# design.net
KiCad netlist of a schematic drawn in Altium Designer
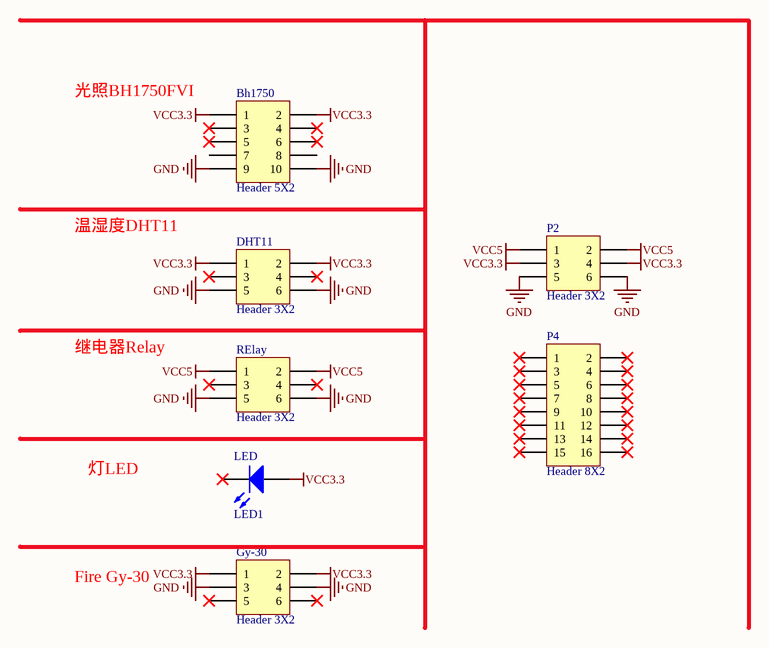
[diagram p0: 智能实验室传感器底板.SchDoc]

(export (version "E")
  (design (tool "Eeschema 10.0.6"))
  (components
    (comp (ref "Bh1750")
      (value "Header 5X2")
      (footprint "HDR2X5")
      (description "Header, 5-Pin, Dual row")
      (fields (field (name "PUBLISHER") "Altium Limited"))
      (libsource (lib "Miscellaneous Connectors") (part "Header 5X2"))
    )
    (comp (ref "DHT11")
      (value "Header 3X2")
      (footprint "HDR2X3")
      (description "Header, 3-Pin, Dual row")
      (fields (field (name "PUBLISHER") "Altium Limited"))
      (libsource (lib "Miscellaneous Connectors") (part "Header 3X2"))
    )
    (comp (ref "Gy-30")
      (value "Header 3X2")
      (footprint "HDR2X3")
      (description "Header, 3-Pin, Dual row")
      (fields (field (name "PUBLISHER") "Altium Limited"))
      (libsource (lib "Miscellaneous Connectors") (part "Header 3X2"))
    )
    (comp (ref "LED")
      (value "LED1")
      (footprint "LED-1")
      (description "Typical RED GaAs LED")
      (fields (field (name "PUBLISHER") "Altium Limited"))
      (libsource (lib "Miscellaneous Devices") (part "LED1"))
    )
    (comp (ref "P2")
      (value "Header 3X2")
      (footprint "HDR2X3")
      (description "Header, 3-Pin, Dual row")
      (fields (field (name "PUBLISHER") "Altium Limited"))
      (libsource (lib "Miscellaneous Connectors") (part "Header 3X2"))
    )
    (comp (ref "P4")
      (value "Header 8X2")
      (footprint "HDR2X8")
      (description "Header, 8-Pin, Dual row")
      (fields (field (name "PUBLISHER") "Altium Limited"))
      (libsource (lib "Miscellaneous Connectors") (part "Header 8X2"))
    )
    (comp (ref "RElay")
      (value "Header 3X2")
      (footprint "HDR2X3")
      (description "Header, 3-Pin, Dual row")
      (fields (field (name "PUBLISHER") "Altium Limited"))
      (libsource (lib "Miscellaneous Connectors") (part "Header 3X2"))
    )
  )
  (nets
    (net (code "1") (name "GND") (class "Default")
      (node (ref "Bh1750") (pin "10") (pinfunction "10_10") (pintype "passive"))
      (node (ref "Bh1750") (pin "9") (pinfunction "9_9") (pintype "passive"))
      (node (ref "DHT11") (pin "5") (pinfunction "5_5") (pintype "passive"))
      (node (ref "DHT11") (pin "6") (pinfunction "6_6") (pintype "passive"))
      (node (ref "Gy-30") (pin "3") (pinfunction "3_3") (pintype "passive"))
      (node (ref "Gy-30") (pin "4") (pinfunction "4_4") (pintype "passive"))
      (node (ref "P2") (pin "5") (pinfunction "5_5") (pintype "passive"))
      (node (ref "P2") (pin "6") (pinfunction "6_6") (pintype "passive"))
      (node (ref "RElay") (pin "5") (pinfunction "5_5") (pintype "passive"))
      (node (ref "RElay") (pin "6") (pinfunction "6_6") (pintype "passive"))
    )
    (net (code "2") (name "VCC3.3") (class "Default")
      (node (ref "Bh1750") (pin "1") (pinfunction "1_1") (pintype "passive"))
      (node (ref "Bh1750") (pin "2") (pinfunction "2_2") (pintype "passive"))
      (node (ref "DHT11") (pin "1") (pinfunction "1_1") (pintype "passive"))
      (node (ref "DHT11") (pin "2") (pinfunction "2_2") (pintype "passive"))
      (node (ref "Gy-30") (pin "1") (pinfunction "1_1") (pintype "passive"))
      (node (ref "Gy-30") (pin "2") (pinfunction "2_2") (pintype "passive"))
      (node (ref "LED") (pin "1") (pinfunction "A_1") (pintype "passive"))
      (node (ref "P2") (pin "3") (pinfunction "3_3") (pintype "passive"))
      (node (ref "P2") (pin "4") (pinfunction "4_4") (pintype "passive"))
    )
    (net (code "3") (name "VCC5") (class "Default")
      (node (ref "P2") (pin "1") (pinfunction "1_1") (pintype "passive"))
      (node (ref "P2") (pin "2") (pinfunction "2_2") (pintype "passive"))
      (node (ref "RElay") (pin "1") (pinfunction "1_1") (pintype "passive"))
      (node (ref "RElay") (pin "2") (pinfunction "2_2") (pintype "passive"))
    )
    (net (code "4") (name "unconnected-(Bh1750-Pad3)") (class "Default")
      (node (ref "Bh1750") (pin "3") (pinfunction "3_3") (pintype "passive+no_connect"))
    )
    (net (code "5") (name "unconnected-(Bh1750-Pad4)") (class "Default")
      (node (ref "Bh1750") (pin "4") (pinfunction "4_4") (pintype "passive+no_connect"))
    )
    (net (code "6") (name "unconnected-(Bh1750-Pad5)") (class "Default")
      (node (ref "Bh1750") (pin "5") (pinfunction "5_5") (pintype "passive+no_connect"))
    )
    (net (code "7") (name "unconnected-(Bh1750-Pad6)") (class "Default")
      (node (ref "Bh1750") (pin "6") (pinfunction "6_6") (pintype "passive+no_connect"))
    )
    (net (code "8") (name "unconnected-(Bh1750-Pad7)") (class "Default")
      (node (ref "Bh1750") (pin "7") (pinfunction "7_7") (pintype "passive"))
    )
    (net (code "9") (name "unconnected-(Bh1750-Pad8)") (class "Default")
      (node (ref "Bh1750") (pin "8") (pinfunction "8_8") (pintype "passive"))
    )
    (net (code "10") (name "unconnected-(DHT11-Pad3)") (class "Default")
      (node (ref "DHT11") (pin "3") (pinfunction "3_3") (pintype "passive+no_connect"))
    )
    (net (code "11") (name "unconnected-(DHT11-Pad4)") (class "Default")
      (node (ref "DHT11") (pin "4") (pinfunction "4_4") (pintype "passive+no_connect"))
    )
    (net (code "12") (name "unconnected-(Gy-30-Pad5)") (class "Default")
      (node (ref "Gy-30") (pin "5") (pinfunction "5_5") (pintype "passive+no_connect"))
    )
    (net (code "13") (name "unconnected-(Gy-30-Pad6)") (class "Default")
      (node (ref "Gy-30") (pin "6") (pinfunction "6_6") (pintype "passive+no_connect"))
    )
    (net (code "14") (name "unconnected-(LED-K-Pad2)") (class "Default")
      (node (ref "LED") (pin "2") (pinfunction "K_2") (pintype "passive+no_connect"))
    )
    (net (code "15") (name "unconnected-(P4-Pad1)") (class "Default")
      (node (ref "P4") (pin "1") (pinfunction "1_1") (pintype "passive+no_connect"))
    )
    (net (code "16") (name "unconnected-(P4-Pad2)") (class "Default")
      (node (ref "P4") (pin "2") (pinfunction "2_2") (pintype "passive+no_connect"))
    )
    (net (code "17") (name "unconnected-(P4-Pad3)") (class "Default")
      (node (ref "P4") (pin "3") (pinfunction "3_3") (pintype "passive+no_connect"))
    )
    (net (code "18") (name "unconnected-(P4-Pad4)") (class "Default")
      (node (ref "P4") (pin "4") (pinfunction "4_4") (pintype "passive+no_connect"))
    )
    (net (code "19") (name "unconnected-(P4-Pad5)") (class "Default")
      (node (ref "P4") (pin "5") (pinfunction "5_5") (pintype "passive+no_connect"))
    )
    (net (code "20") (name "unconnected-(P4-Pad6)") (class "Default")
      (node (ref "P4") (pin "6") (pinfunction "6_6") (pintype "passive+no_connect"))
    )
    (net (code "21") (name "unconnected-(P4-Pad7)") (class "Default")
      (node (ref "P4") (pin "7") (pinfunction "7_7") (pintype "passive+no_connect"))
    )
    (net (code "22") (name "unconnected-(P4-Pad8)") (class "Default")
      (node (ref "P4") (pin "8") (pinfunction "8_8") (pintype "passive+no_connect"))
    )
    (net (code "23") (name "unconnected-(P4-Pad9)") (class "Default")
      (node (ref "P4") (pin "9") (pinfunction "9_9") (pintype "passive+no_connect"))
    )
    (net (code "24") (name "unconnected-(P4-Pad10)") (class "Default")
      (node (ref "P4") (pin "10") (pinfunction "10_10") (pintype "passive+no_connect"))
    )
    (net (code "25") (name "unconnected-(P4-Pad11)") (class "Default")
      (node (ref "P4") (pin "11") (pinfunction "11_11") (pintype "passive+no_connect"))
    )
    (net (code "26") (name "unconnected-(P4-Pad12)") (class "Default")
      (node (ref "P4") (pin "12") (pinfunction "12_12") (pintype "passive+no_connect"))
    )
    (net (code "27") (name "unconnected-(P4-Pad13)") (class "Default")
      (node (ref "P4") (pin "13") (pinfunction "13_13") (pintype "passive+no_connect"))
    )
    (net (code "28") (name "unconnected-(P4-Pad14)") (class "Default")
      (node (ref "P4") (pin "14") (pinfunction "14_14") (pintype "passive+no_connect"))
    )
    (net (code "29") (name "unconnected-(P4-Pad15)") (class "Default")
      (node (ref "P4") (pin "15") (pinfunction "15_15") (pintype "passive+no_connect"))
    )
    (net (code "30") (name "unconnected-(P4-Pad16)") (class "Default")
      (node (ref "P4") (pin "16") (pinfunction "16_16") (pintype "passive+no_connect"))
    )
    (net (code "31") (name "unconnected-(RElay-Pad3)") (class "Default")
      (node (ref "RElay") (pin "3") (pinfunction "3_3") (pintype "passive+no_connect"))
    )
    (net (code "32") (name "unconnected-(RElay-Pad4)") (class "Default")
      (node (ref "RElay") (pin "4") (pinfunction "4_4") (pintype "passive+no_connect"))
    )
  )
)
